# 01-Antennas.net
KiCad netlist of a schematic drawn in Altium Designer
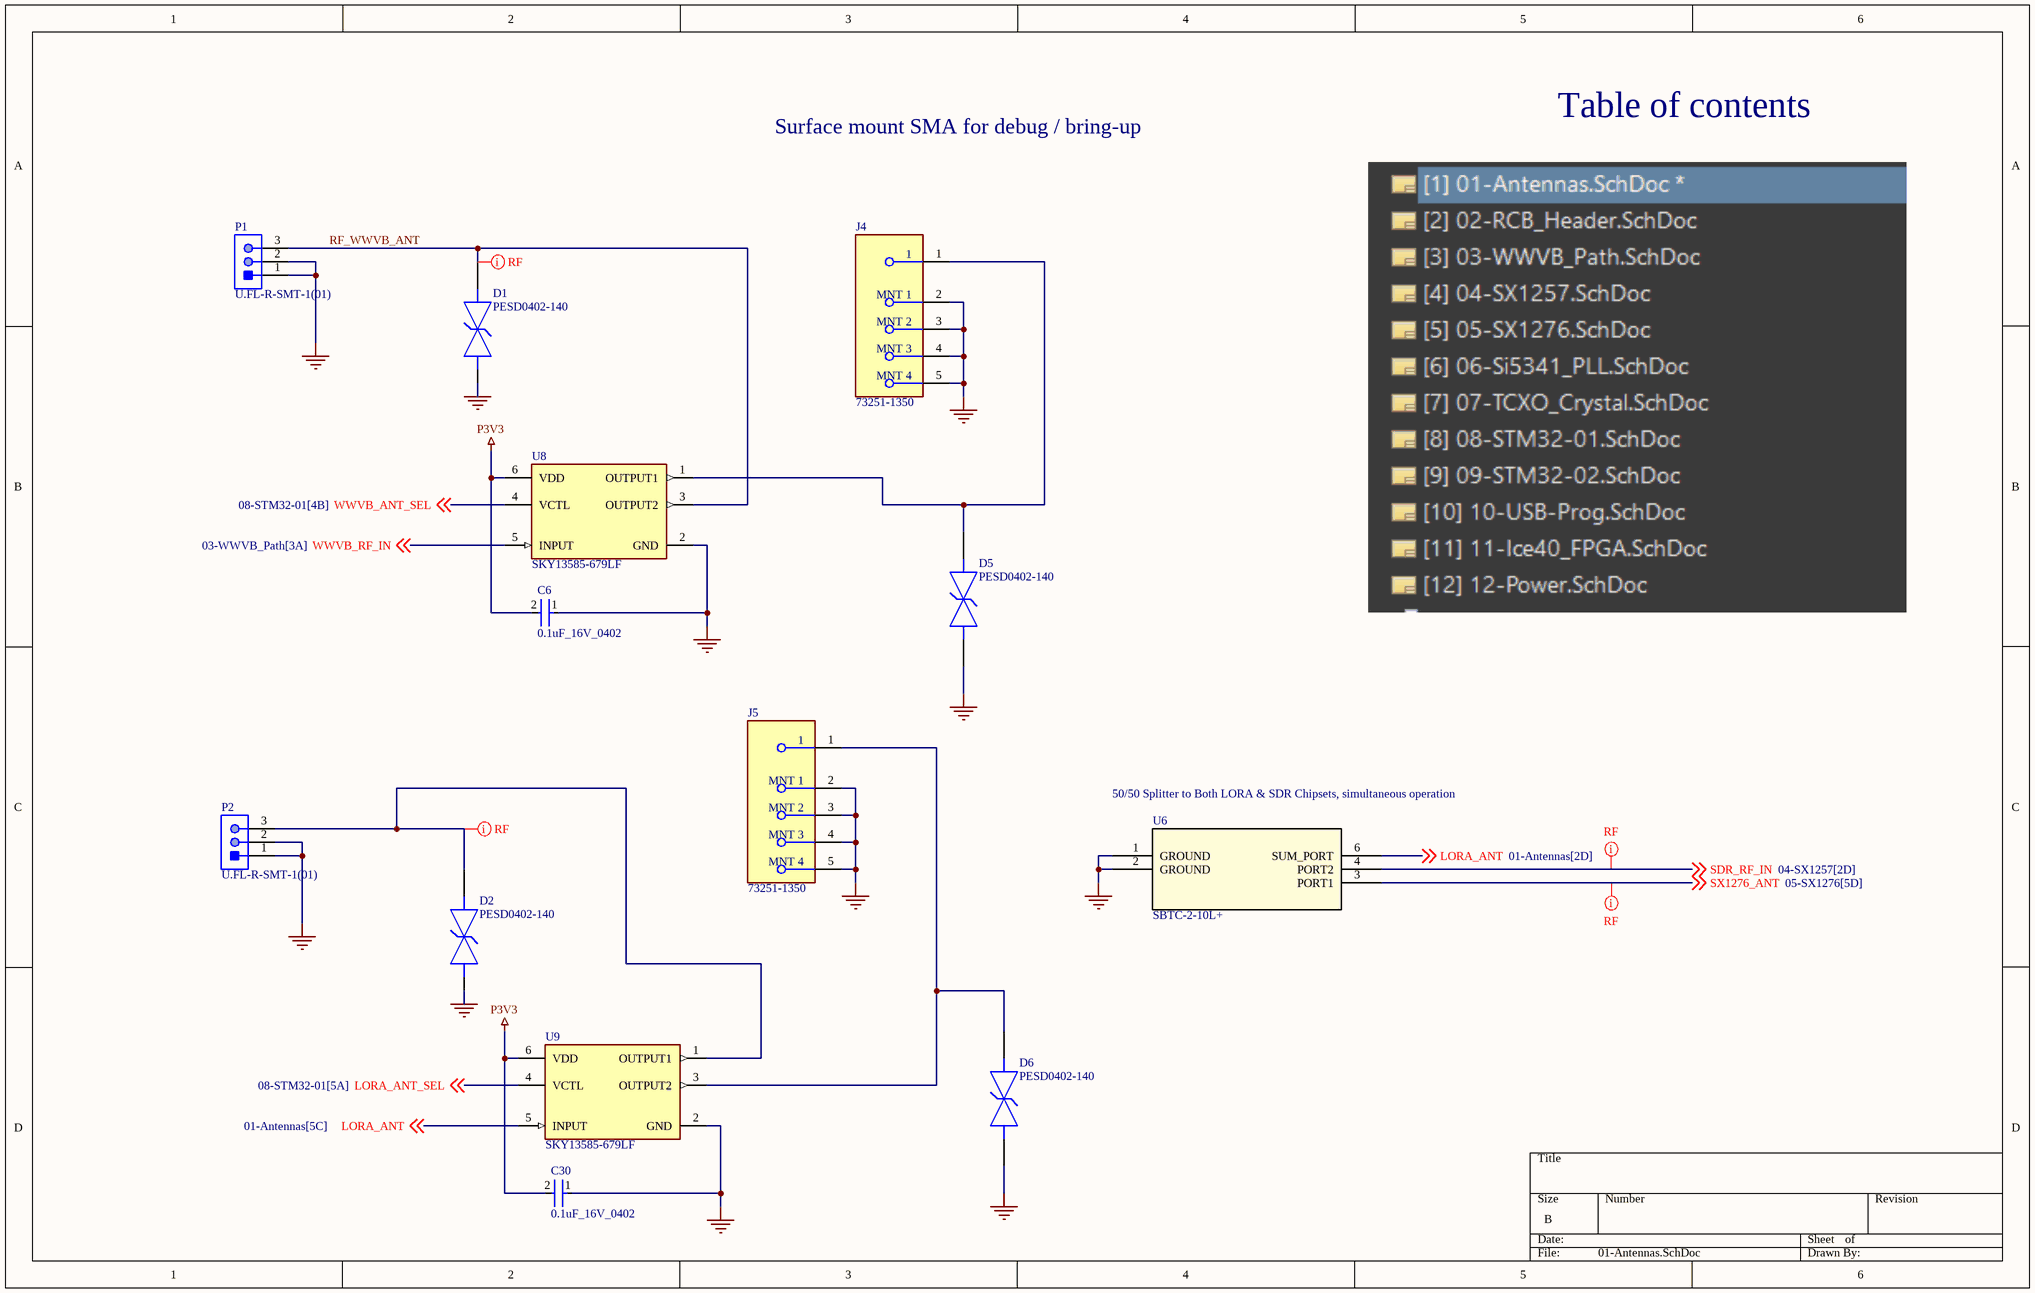
[diagram p0: 01-Antennas.SchDoc]

(export (version "E")
  (design (tool "Eeschema 10.0.6"))
  (components
    (comp (ref "C6")
      (value "0.1uF_16V_0402")
      (footprint "FP-C0402-BB-MFG")
      (description "CAP CER 0.1UF 16V 5% X7R 0402")
      (fields
        (field (name "MANUFACTURER") "Kemet")
        (field (name "MANUFACTURER PART NUMBER") "C0402C104J4RACTU")
      )
      (libsource (lib "Altium Content Vault") (part "b4654b650e69147ec39a6b967a45e02"))
    )
    (comp (ref "C30")
      (value "0.1uF_16V_0402")
      (footprint "FP-C0402-BB-MFG")
      (description "CAP CER 0.1UF 16V 5% X7R 0402")
      (fields
        (field (name "MANUFACTURER") "Kemet")
        (field (name "MANUFACTURER PART NUMBER") "C0402C104J4RACTU")
      )
      (libsource (lib "Altium Content Vault") (part "b4654b650e69147ec39a6b967a45e02"))
    )
    (comp (ref "D1")
      (value "PESD0402-140")
      (footprint "FP-PESD0402-MFG")
      (description "TVS DIODE 14V 40V 0402")
      (fields
        (field (name "OCTOPART") "https://octopart.com/pesd0402-140-littelfuse-74215061")
        (field (name "MANUFACTURER") "Littelfuse Inc.")
      )
      (libsource (lib "Altium Content Vault") (part "edccc070dd5cba1f9372128faf3915e"))
    )
    (comp (ref "D2")
      (value "PESD0402-140")
      (footprint "FP-PESD0402-MFG")
      (description "TVS DIODE 14V 40V 0402")
      (fields
        (field (name "OCTOPART") "https://octopart.com/pesd0402-140-littelfuse-74215061")
        (field (name "MANUFACTURER") "Littelfuse Inc.")
      )
      (libsource (lib "Altium Content Vault") (part "edccc070dd5cba1f9372128faf3915e"))
    )
    (comp (ref "D5")
      (value "PESD0402-140")
      (footprint "FP-PESD0402-MFG")
      (description "TVS DIODE 14V 40V 0402")
      (fields
        (field (name "OCTOPART") "https://octopart.com/pesd0402-140-littelfuse-74215061")
        (field (name "MANUFACTURER") "Littelfuse Inc.")
      )
      (libsource (lib "Altium Content Vault") (part "edccc070dd5cba1f9372128faf3915e"))
    )
    (comp (ref "D6")
      (value "PESD0402-140")
      (footprint "FP-PESD0402-MFG")
      (description "TVS DIODE 14V 40V 0402")
      (fields
        (field (name "OCTOPART") "https://octopart.com/pesd0402-140-littelfuse-74215061")
        (field (name "MANUFACTURER") "Littelfuse Inc.")
      )
      (libsource (lib "Altium Content Vault") (part "edccc070dd5cba1f9372128faf3915e"))
    )
    (comp (ref "J4")
      (value "73251-1350")
      (footprint "FP-73251-1350-MFG")
      (description "CONN SMA JACK STR 50 OHM SMD")
      (fields
        (field (name "OCTOPART") "https://octopart.com/73251-1350-molex-5414390")
        (field (name "MANUFACTURER") "Molex")
      )
      (libsource (lib "Altium Content Vault") (part "474d33b8a96b1ade9ed6dd87a2b06d4"))
    )
    (comp (ref "J5")
      (value "73251-1350")
      (footprint "FP-73251-1350-MFG")
      (description "CONN SMA JACK STR 50 OHM SMD")
      (fields
        (field (name "OCTOPART") "https://octopart.com/73251-1350-molex-5414390")
        (field (name "MANUFACTURER") "Molex")
      )
      (libsource (lib "Altium Content Vault") (part "474d33b8a96b1ade9ed6dd87a2b06d4"))
    )
    (comp (ref "P1")
      (value "U.FL-R-SMT-1(01)")
      (footprint "HRS-U.FL-R-SMT-3_V")
      (description "Ultra Small Coaxial Connector, 6 GHz, -40 to 90 degC, 3-Pin SMD, RoHS, Bulk")
      (fields (field (name "MANUFACTURER") "Hirose Electric"))
      (libsource (lib "Altium Content Vault") (part "CN-1P-M-R3"))
    )
    (comp (ref "P2")
      (value "U.FL-R-SMT-1(01)")
      (footprint "HRS-U.FL-R-SMT-3_V")
      (description "Ultra Small Coaxial Connector, 6 GHz, -40 to 90 degC, 3-Pin SMD, RoHS, Bulk")
      (fields (field (name "MANUFACTURER") "Hirose Electric"))
      (libsource (lib "Altium Content Vault") (part "CN-1P-M-R3"))
    )
    (comp (ref "U6")
      (value "SBTC-2-10L+")
      (footprint "AT1029_MNC")
      (description "No Description Available")
      (fields (field (name "COPYRIGHT") "Copyright (C) 2023 Ultra Librarian. All rights reserved."))
      (libsource (lib "SBTC-2-10L&plus_") (part "SBTC-2-10L+"))
    )
    (comp (ref "U8")
      (value "SKY13585-679LF")
      (footprint "FP-SKY13585-679LF-MFG")
      (description "IC RF SWITCH SPDT 6GHZ 6MLPD")
      (libsource (lib "Altium Content Vault") (part "e67e48af39ab44f3294fce00d3e4f12"))
    )
    (comp (ref "U9")
      (value "SKY13585-679LF")
      (footprint "FP-SKY13585-679LF-MFG")
      (description "IC RF SWITCH SPDT 6GHZ 6MLPD")
      (libsource (lib "Altium Content Vault") (part "e67e48af39ab44f3294fce00d3e4f12"))
    )
  )
  (nets
    (net (code "1") (name "/RF_WWVB_ANT") (class "Default")
      (node (ref "D1") (pin "2") (pinfunction "2_2") (pintype "passive"))
      (node (ref "P1") (pin "3") (pinfunction "3_3") (pintype "passive"))
      (node (ref "U8") (pin "3") (pinfunction "OUTPUT2_3") (pintype "output"))
    )
    (net (code "2") (name "GND") (class "Default")
      (node (ref "C30") (pin "1") (pinfunction "1_1") (pintype "passive"))
      (node (ref "C6") (pin "1") (pinfunction "1_1") (pintype "passive"))
      (node (ref "D1") (pin "1") (pinfunction "1_1") (pintype "passive"))
      (node (ref "D2") (pin "1") (pinfunction "1_1") (pintype "passive"))
      (node (ref "D5") (pin "1") (pinfunction "1_1") (pintype "passive"))
      (node (ref "D6") (pin "1") (pinfunction "1_1") (pintype "passive"))
      (node (ref "J4") (pin "2") (pinfunction "MNT_1_2") (pintype "passive"))
      (node (ref "J4") (pin "3") (pinfunction "MNT_2_3") (pintype "passive"))
      (node (ref "J4") (pin "4") (pinfunction "MNT_3_4") (pintype "passive"))
      (node (ref "J4") (pin "5") (pinfunction "MNT_4_5") (pintype "passive"))
      (node (ref "J5") (pin "2") (pinfunction "MNT_1_2") (pintype "passive"))
      (node (ref "J5") (pin "3") (pinfunction "MNT_2_3") (pintype "passive"))
      (node (ref "J5") (pin "4") (pinfunction "MNT_3_4") (pintype "passive"))
      (node (ref "J5") (pin "5") (pinfunction "MNT_4_5") (pintype "passive"))
      (node (ref "P1") (pin "1") (pinfunction "1_1") (pintype "passive"))
      (node (ref "P1") (pin "2") (pinfunction "2_2") (pintype "passive"))
      (node (ref "P2") (pin "1") (pinfunction "1_1") (pintype "passive"))
      (node (ref "P2") (pin "2") (pinfunction "2_2") (pintype "passive"))
      (node (ref "U6") (pin "1") (pinfunction "GROUND_1") (pintype "passive"))
      (node (ref "U6") (pin "2") (pinfunction "GROUND_2") (pintype "passive"))
      (node (ref "U8") (pin "2") (pinfunction "GND_2") (pintype "power_in"))
      (node (ref "U9") (pin "2") (pinfunction "GND_2") (pintype "power_in"))
    )
    (net (code "3") (name "LORA_ANT") (class "Default")
      (node (ref "U6") (pin "6") (pinfunction "SUM_PORT_6") (pintype "passive"))
      (node (ref "U9") (pin "5") (pinfunction "INPUT_5") (pintype "input"))
    )
    (net (code "4") (name "LORA_ANT_SEL") (class "Default")
      (node (ref "U9") (pin "4") (pinfunction "VCTL_4") (pintype "power_in"))
    )
    (net (code "5") (name "Net-(U8-OUTPUT1)") (class "Default")
      (node (ref "D5") (pin "2") (pinfunction "2_2") (pintype "passive"))
      (node (ref "J4") (pin "1") (pinfunction "1_1") (pintype "passive"))
      (node (ref "U8") (pin "1") (pinfunction "OUTPUT1_1") (pintype "output"))
    )
    (net (code "6") (name "Net-(U9-OUTPUT1)") (class "Default")
      (node (ref "D2") (pin "2") (pinfunction "2_2") (pintype "passive"))
      (node (ref "P2") (pin "3") (pinfunction "3_3") (pintype "passive"))
      (node (ref "U9") (pin "1") (pinfunction "OUTPUT1_1") (pintype "output"))
    )
    (net (code "7") (name "Net-(U9-OUTPUT2)") (class "Default")
      (node (ref "D6") (pin "2") (pinfunction "2_2") (pintype "passive"))
      (node (ref "J5") (pin "1") (pinfunction "1_1") (pintype "passive"))
      (node (ref "U9") (pin "3") (pinfunction "OUTPUT2_3") (pintype "output"))
    )
    (net (code "8") (name "P3V3") (class "Default")
      (node (ref "C30") (pin "2") (pinfunction "2_2") (pintype "passive"))
      (node (ref "C6") (pin "2") (pinfunction "2_2") (pintype "passive"))
      (node (ref "U8") (pin "6") (pinfunction "VDD_6") (pintype "power_in"))
      (node (ref "U9") (pin "6") (pinfunction "VDD_6") (pintype "power_in"))
    )
    (net (code "9") (name "SDR_RF_IN") (class "Default")
      (node (ref "U6") (pin "4") (pinfunction "PORT2_4") (pintype "passive"))
    )
    (net (code "10") (name "SX1276_ANT") (class "Default")
      (node (ref "U6") (pin "3") (pinfunction "PORT1_3") (pintype "passive"))
    )
    (net (code "11") (name "WWVB_ANT_SEL") (class "Default")
      (node (ref "U8") (pin "4") (pinfunction "VCTL_4") (pintype "power_in"))
    )
    (net (code "12") (name "WWVB_RF_IN") (class "Default")
      (node (ref "U8") (pin "5") (pinfunction "INPUT_5") (pintype "input"))
    )
  )
)
